# IsolatedADC.net
KiCad netlist of a schematic drawn in Altium Designer
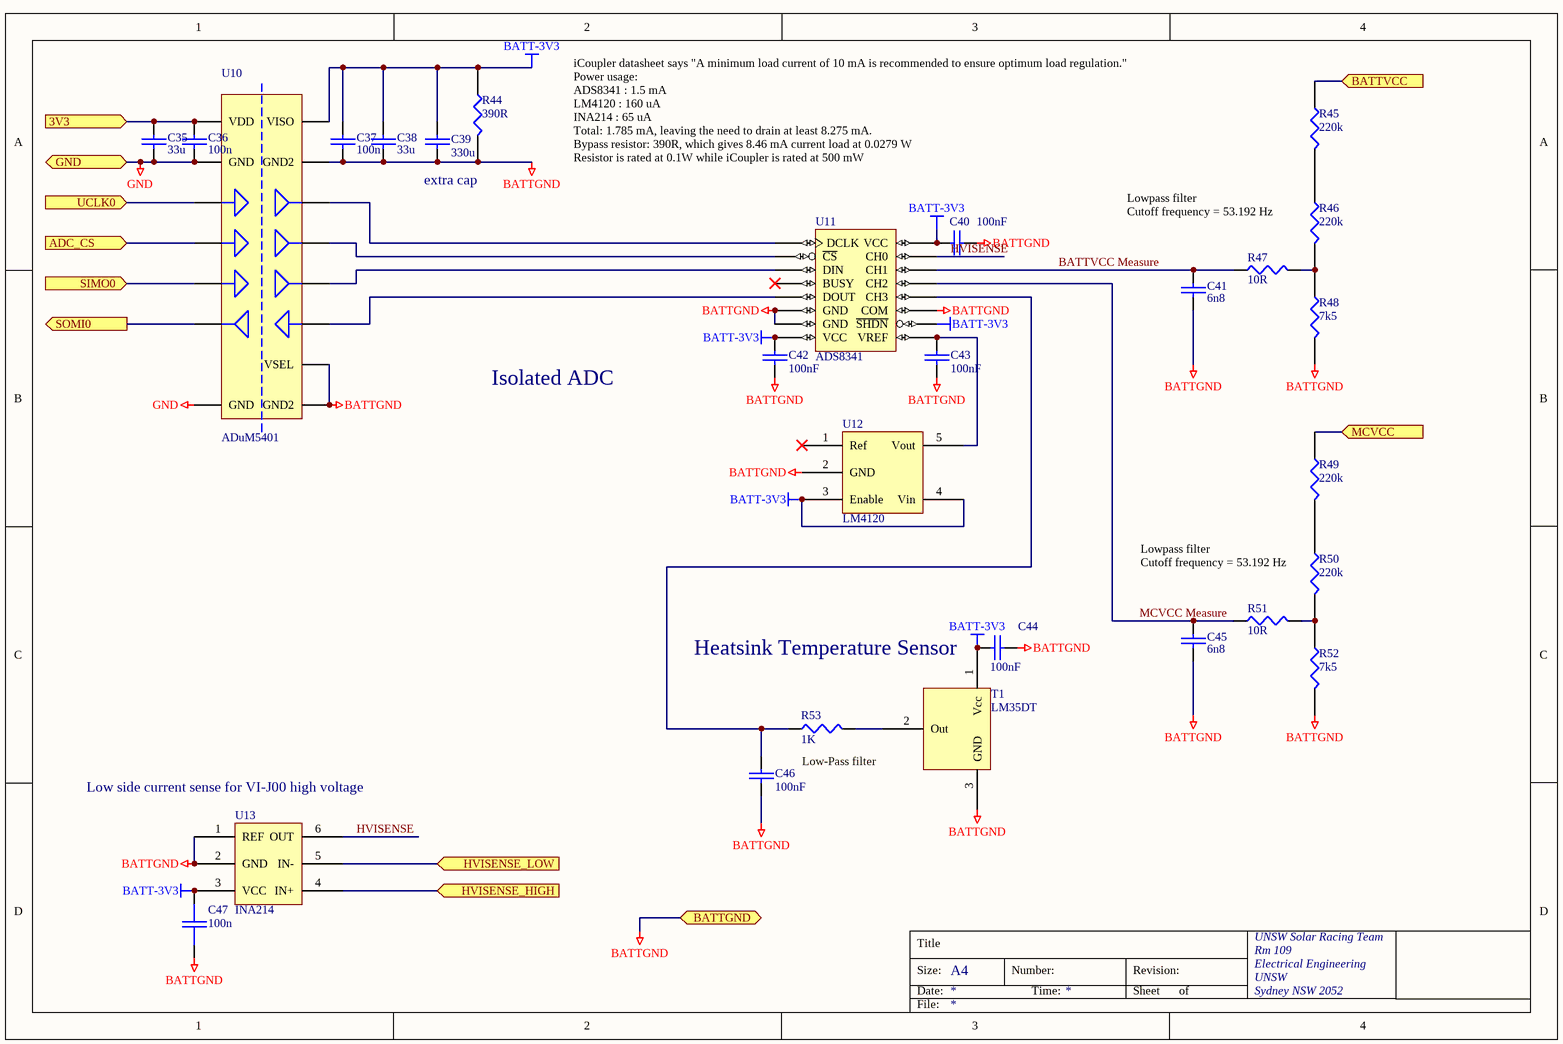
[diagram p0: IsolatedADC.SCHDOC]

(export (version "E")
  (design (tool "Eeschema 10.0.6"))
  (components
    (comp (ref "C35")
      (value "33u")
      (footprint "MCCT-CASEB")
      (description "Capacitor")
      (libsource (lib "*") (part "CAP"))
    )
    (comp (ref "C36")
      (value "100n")
      (footprint "0603")
      (description "Capacitor")
      (libsource (lib "*") (part "CAP"))
    )
    (comp (ref "C37")
      (value "100n")
      (footprint "0603")
      (description "Capacitor")
      (libsource (lib "*") (part "CAP"))
    )
    (comp (ref "C38")
      (value "33u")
      (footprint "MCCT-CASEB")
      (description "Capacitor")
      (libsource (lib "*") (part "CAP"))
    )
    (comp (ref "C39")
      (value "330u")
      (footprint "KEMET_CASED")
      (description "Capacitor")
      (libsource (lib "*") (part "CAP"))
    )
    (comp (ref "C40")
      (value "100nF")
      (footprint "0603")
      (description "Capacitor")
      (libsource (lib "*") (part "CAP"))
    )
    (comp (ref "C41")
      (value "6n8")
      (footprint "0603")
      (description "Capacitor")
      (libsource (lib "*") (part "CAP"))
    )
    (comp (ref "C42")
      (value "100nF")
      (footprint "0603")
      (description "Capacitor")
      (libsource (lib "*") (part "CAP"))
    )
    (comp (ref "C43")
      (value "100nF")
      (footprint "0603")
      (description "Capacitor")
      (libsource (lib "*") (part "CAP"))
    )
    (comp (ref "C44")
      (value "100nF")
      (footprint "0603")
      (description "Capacitor")
      (libsource (lib "*") (part "CAP"))
    )
    (comp (ref "C45")
      (value "6n8")
      (footprint "0603")
      (description "Capacitor")
      (libsource (lib "*") (part "CAP"))
    )
    (comp (ref "C46")
      (value "100nF")
      (footprint "0603")
      (description "Capacitor")
      (libsource (lib "*") (part "CAP"))
    )
    (comp (ref "C47")
      (value "100n")
      (footprint "0603")
      (description "Capacitor")
      (libsource (lib "") (part "CAP_1"))
    )
    (comp (ref "R44") (value "390R") (footprint "0603") (libsource (lib "*") (part "RES1")))
    (comp (ref "R45") (value "220k") (footprint "1206") (libsource (lib "*") (part "RES1")))
    (comp (ref "R46") (value "220k") (footprint "1206") (libsource (lib "*") (part "RES1")))
    (comp (ref "R47")
      (value "10R")
      (footprint "0603")
      (description "Resistor")
      (libsource (lib "RCLDQ") (part "RES1"))
    )
    (comp (ref "R48") (value "7k5") (footprint "1206") (libsource (lib "*") (part "RES1")))
    (comp (ref "R49") (value "220k") (footprint "1206") (libsource (lib "*") (part "RES1")))
    (comp (ref "R50") (value "220k") (footprint "1206") (libsource (lib "*") (part "RES1")))
    (comp (ref "R51")
      (value "10R")
      (footprint "0603")
      (description "Resistor")
      (libsource (lib "RCLDQ") (part "RES1"))
    )
    (comp (ref "R52") (value "7k5") (footprint "1206") (libsource (lib "*") (part "RES1")))
    (comp (ref "R53")
      (value "1K")
      (footprint "0603")
      (description "Resistor")
      (libsource (lib "SunswiftLib20030312RR") (part "RES1"))
    )
    (comp (ref "T1")
      (value "LM35DT")
      (footprint "TO-220-up")
      (description "Temperature Sensor")
      (libsource (lib "SUNSWIFTLIB") (part "LM35DZ"))
    )
    (comp (ref "U10")
      (value "ADuM5401")
      (footprint "SOIC_W16")
      (description "Optocoupler w/ DCDC")
      (libsource (lib "Optocouplers") (part "ADuM5401"))
    )
    (comp (ref "U11") (value "ADS8341") (footprint "TSSOP16") (libsource (lib "*") (part "ADS8341")))
    (comp (ref "U12")
      (value "LM4120")
      (footprint "SOT23-5")
      (description "Precision LDO voltage reference")
      (libsource (lib "*") (part "LM4120"))
    )
    (comp (ref "U13")
      (value "INA214")
      (footprint "SC70-6")
      (description "Current Sensor")
      (libsource (lib "MiscellaneousIC") (part "INA214"))
    )
  )
  (nets
    (net (code "1") (name "/3V3") (class "Default")
      (node (ref "C35") (pin "2") (pinfunction "2_2") (pintype "passive"))
      (node (ref "C36") (pin "2") (pinfunction "2_2") (pintype "passive"))
      (node (ref "U10") (pin "1") (pinfunction "VDD_1") (pintype "passive"))
    )
    (net (code "2") (name "/ADC_CS") (class "Default")
      (node (ref "U10") (pin "4") (pinfunction "IN2_4") (pintype "passive"))
    )
    (net (code "3") (name "/BATTVCC") (class "Default")
      (node (ref "R45") (pin "1") (pinfunction "1_1") (pintype "passive"))
    )
    (net (code "4") (name "/BATTVCC Measure") (class "Default")
      (node (ref "C41") (pin "1") (pinfunction "1_1") (pintype "passive"))
      (node (ref "R47") (pin "1") (pinfunction "1_1") (pintype "passive"))
      (node (ref "U11") (pin "3") (pinfunction "CH1_3") (pintype "bidirectional"))
    )
    (net (code "5") (name "/HVISENSE") (class "Default")
      (node (ref "U11") (pin "2") (pinfunction "CH0_2") (pintype "bidirectional"))
      (node (ref "U13") (pin "6") (pinfunction "OUT_6") (pintype "passive"))
    )
    (net (code "6") (name "/HVISENSE_HIGH") (class "Default")
      (node (ref "U13") (pin "4") (pinfunction "IN+_4") (pintype "passive"))
    )
    (net (code "7") (name "/HVISENSE_LOW") (class "Default")
      (node (ref "U13") (pin "5") (pinfunction "IN-_5") (pintype "passive"))
    )
    (net (code "8") (name "/MCVCC") (class "Default")
      (node (ref "R49") (pin "1") (pinfunction "1_1") (pintype "passive"))
    )
    (net (code "9") (name "/MCVCC Measure") (class "Default")
      (node (ref "C45") (pin "1") (pinfunction "1_1") (pintype "passive"))
      (node (ref "R51") (pin "1") (pinfunction "1_1") (pintype "passive"))
      (node (ref "U11") (pin "4") (pinfunction "CH2_4") (pintype "bidirectional"))
    )
    (net (code "10") (name "/SIMO0") (class "Default")
      (node (ref "U10") (pin "5") (pinfunction "IN3_5") (pintype "passive"))
    )
    (net (code "11") (name "/SOMI0") (class "Default")
      (node (ref "U10") (pin "6") (pinfunction "OUT4_6") (pintype "passive"))
    )
    (net (code "12") (name "/UCLK0") (class "Default")
      (node (ref "U10") (pin "3") (pinfunction "IN1_3") (pintype "passive"))
    )
    (net (code "13") (name "BATT-3V3") (class "Default")
      (node (ref "C37") (pin "2") (pinfunction "2_2") (pintype "passive"))
      (node (ref "C38") (pin "2") (pinfunction "2_2") (pintype "passive"))
      (node (ref "C39") (pin "1") (pinfunction "1_1") (pintype "passive"))
      (node (ref "C40") (pin "1") (pinfunction "1_1") (pintype "passive"))
      (node (ref "C42") (pin "2") (pinfunction "2_2") (pintype "passive"))
      (node (ref "C44") (pin "1") (pinfunction "1_1") (pintype "passive"))
      (node (ref "C47") (pin "2") (pinfunction "2_2") (pintype "passive"))
      (node (ref "R44") (pin "1") (pinfunction "1_1") (pintype "passive"))
      (node (ref "T1") (pin "1") (pinfunction "Vcc_1") (pintype "power_in"))
      (node (ref "U10") (pin "16") (pinfunction "VISO_16") (pintype "passive"))
      (node (ref "U11") (pin "1") (pinfunction "VCC_1") (pintype "bidirectional"))
      (node (ref "U11") (pin "7") (pinfunction "SHDN_7") (pintype "bidirectional"))
      (node (ref "U11") (pin "9") (pinfunction "VCC_9") (pintype "bidirectional"))
      (node (ref "U12") (pin "3") (pinfunction "Enable_3") (pintype "passive"))
      (node (ref "U12") (pin "4") (pinfunction "Vin_4") (pintype "passive"))
      (node (ref "U13") (pin "3") (pinfunction "VCC_3") (pintype "passive"))
    )
    (net (code "14") (name "BATTGND") (class "Default")
      (node (ref "C37") (pin "1") (pinfunction "1_1") (pintype "passive"))
      (node (ref "C38") (pin "1") (pinfunction "1_1") (pintype "passive"))
      (node (ref "C39") (pin "2") (pinfunction "2_2") (pintype "passive"))
      (node (ref "C40") (pin "2") (pinfunction "2_2") (pintype "passive"))
      (node (ref "C41") (pin "2") (pinfunction "2_2") (pintype "passive"))
      (node (ref "C42") (pin "1") (pinfunction "1_1") (pintype "passive"))
      (node (ref "C43") (pin "2") (pinfunction "2_2") (pintype "passive"))
      (node (ref "C44") (pin "2") (pinfunction "2_2") (pintype "passive"))
      (node (ref "C45") (pin "2") (pinfunction "2_2") (pintype "passive"))
      (node (ref "C46") (pin "2") (pinfunction "2_2") (pintype "passive"))
      (node (ref "C47") (pin "1") (pinfunction "1_1") (pintype "passive"))
      (node (ref "R44") (pin "2") (pinfunction "2_2") (pintype "passive"))
      (node (ref "R48") (pin "2") (pinfunction "2_2") (pintype "passive"))
      (node (ref "R52") (pin "2") (pinfunction "2_2") (pintype "passive"))
      (node (ref "T1") (pin "3") (pinfunction "GND_3") (pintype "passive"))
      (node (ref "U10") (pin "10") (pinfunction "VSEL_10") (pintype "passive"))
      (node (ref "U10") (pin "15") (pinfunction "GND2_15") (pintype "passive"))
      (node (ref "U10") (pin "9") (pinfunction "GND2_9") (pintype "passive"))
      (node (ref "U11") (pin "10") (pinfunction "GND_10") (pintype "bidirectional"))
      (node (ref "U11") (pin "11") (pinfunction "GND_11") (pintype "bidirectional"))
      (node (ref "U11") (pin "6") (pinfunction "COM_6") (pintype "bidirectional"))
      (node (ref "U12") (pin "2") (pinfunction "GND_2") (pintype "passive"))
      (node (ref "U13") (pin "1") (pinfunction "REF_1") (pintype "passive"))
      (node (ref "U13") (pin "2") (pinfunction "GND_2") (pintype "passive"))
    )
    (net (code "15") (name "GND") (class "Default")
      (node (ref "C35") (pin "1") (pinfunction "1_1") (pintype "passive"))
      (node (ref "C36") (pin "1") (pinfunction "1_1") (pintype "passive"))
      (node (ref "U10") (pin "2") (pinfunction "GND_2") (pintype "passive"))
      (node (ref "U10") (pin "8") (pinfunction "GND_8") (pintype "passive"))
    )
    (net (code "16") (name "Net-(R45-Pad2)") (class "Default")
      (node (ref "R45") (pin "2") (pinfunction "2_2") (pintype "passive"))
      (node (ref "R46") (pin "1") (pinfunction "1_1") (pintype "passive"))
    )
    (net (code "17") (name "Net-(R46-Pad2)") (class "Default")
      (node (ref "R46") (pin "2") (pinfunction "2_2") (pintype "passive"))
      (node (ref "R47") (pin "2") (pinfunction "2_2") (pintype "passive"))
      (node (ref "R48") (pin "1") (pinfunction "1_1") (pintype "passive"))
    )
    (net (code "18") (name "Net-(R49-Pad2)") (class "Default")
      (node (ref "R49") (pin "2") (pinfunction "2_2") (pintype "passive"))
      (node (ref "R50") (pin "1") (pinfunction "1_1") (pintype "passive"))
    )
    (net (code "19") (name "Net-(R50-Pad2)") (class "Default")
      (node (ref "R50") (pin "2") (pinfunction "2_2") (pintype "passive"))
      (node (ref "R51") (pin "2") (pinfunction "2_2") (pintype "passive"))
      (node (ref "R52") (pin "1") (pinfunction "1_1") (pintype "passive"))
    )
    (net (code "20") (name "Net-(T1-Out)") (class "Default")
      (node (ref "R53") (pin "2") (pinfunction "2_2") (pintype "passive"))
      (node (ref "T1") (pin "2") (pinfunction "Out_2") (pintype "passive"))
    )
    (net (code "21") (name "Net-(U10-IN4)") (class "Default")
      (node (ref "U10") (pin "11") (pinfunction "IN4_11") (pintype "passive"))
      (node (ref "U11") (pin "12") (pinfunction "DOUT_12") (pintype "bidirectional"))
    )
    (net (code "22") (name "Net-(U10-OUT1)") (class "Default")
      (node (ref "U10") (pin "14") (pinfunction "OUT1_14") (pintype "passive"))
      (node (ref "U11") (pin "16") (pinfunction "DCLK_16") (pintype "bidirectional"))
    )
    (net (code "23") (name "Net-(U10-OUT2)") (class "Default")
      (node (ref "U10") (pin "13") (pinfunction "OUT2_13") (pintype "passive"))
      (node (ref "U11") (pin "15") (pinfunction "CS_15") (pintype "bidirectional"))
    )
    (net (code "24") (name "Net-(U10-OUT3)") (class "Default")
      (node (ref "U10") (pin "12") (pinfunction "OUT3_12") (pintype "passive"))
      (node (ref "U11") (pin "14") (pinfunction "DIN_14") (pintype "bidirectional"))
    )
    (net (code "25") (name "Net-(U11-CH3)") (class "Default")
      (node (ref "C46") (pin "1") (pinfunction "1_1") (pintype "passive"))
      (node (ref "R53") (pin "1") (pinfunction "1_1") (pintype "passive"))
      (node (ref "U11") (pin "5") (pinfunction "CH3_5") (pintype "bidirectional"))
    )
    (net (code "26") (name "Net-(U11-VREF)") (class "Default")
      (node (ref "C43") (pin "1") (pinfunction "1_1") (pintype "passive"))
      (node (ref "U11") (pin "8") (pinfunction "VREF_8") (pintype "bidirectional"))
      (node (ref "U12") (pin "5") (pinfunction "Vout_5") (pintype "passive"))
    )
    (net (code "27") (name "unconnected-(U11-BUSY-Pad13)") (class "Default")
      (node (ref "U11") (pin "13") (pinfunction "BUSY_13") (pintype "bidirectional+no_connect"))
    )
    (net (code "28") (name "unconnected-(U12-Ref-Pad1)") (class "Default")
      (node (ref "U12") (pin "1") (pinfunction "Ref_1") (pintype "passive+no_connect"))
    )
  )
)
